# 03_-_CONNECTORS.net
KiCad netlist of a schematic drawn in Altium Designer
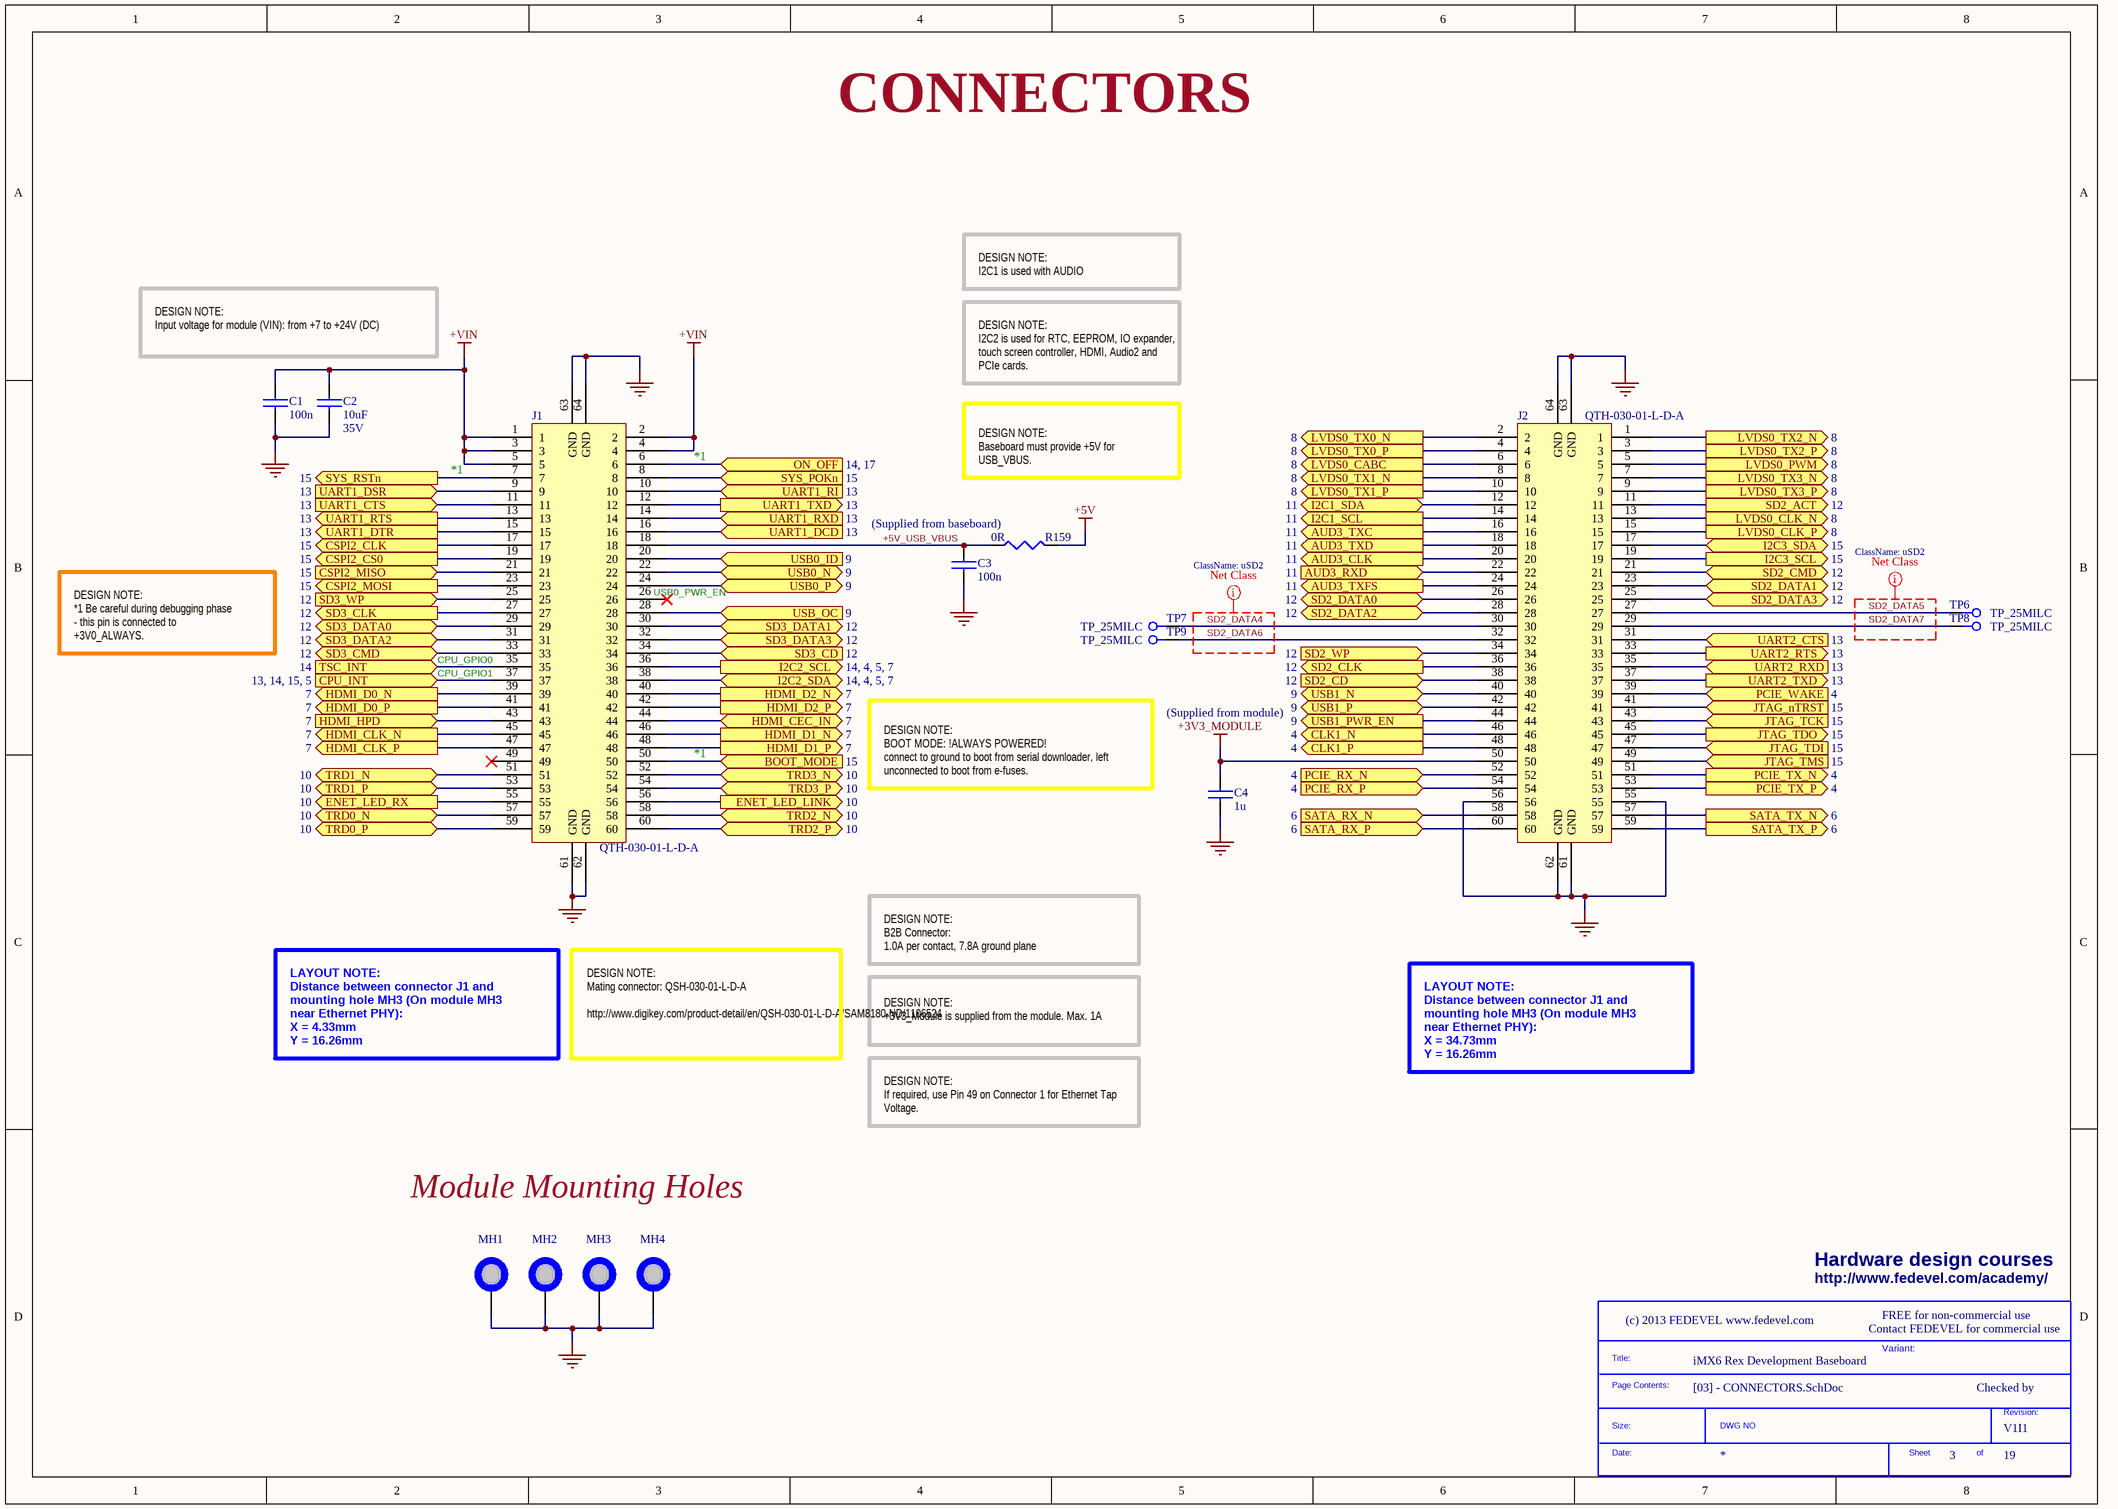
[diagram p0: [03] - CONNECTORS.SchDoc]

(export (version "E")
  (design (tool "Eeschema 10.0.6"))
  (components
    (comp (ref "C1")
      (value "100n")
      (footprint "C0402")
      (description "CAP CER .10UF 50V X5R 10% 0402")
      (fields
        (field (name "MANUFACTURER") "TDK Corporation")
        (field (name "MANUFACTURER PART NUMBER") "C1005X5R1H104K")
      )
      (libsource (lib "Integrated_Library_RF_FEB_2012") (part "C1005X5R1H104K"))
    )
    (comp (ref "C2")
      (value "10uF")
      (footprint "C1206")
      (description "CAP CER 10UF 35V X5R 1206")
      (fields
        (field (name "MANUFACTURER") "Murata Electronics North America")
        (field (name "MANUFACTURER PART NUMBER") "GRM31CR6YA106KA12L")
        (field (name "VOLTAGE - RATED") "35V")
      )
      (libsource (lib "Integrated_Library_RF_FEB_2012") (part "GRM31CR6YA106KA12L"))
    )
    (comp (ref "C3")
      (value "100n")
      (footprint "C0402")
      (description "CAP CER .10UF 50V X5R 10% 0402")
      (fields
        (field (name "MANUFACTURER") "TDK Corporation")
        (field (name "MANUFACTURER PART NUMBER") "C1005X5R1H104K")
      )
      (libsource (lib "Integrated_Library_RF_FEB_2012") (part "C1005X5R1H104K"))
    )
    (comp (ref "C4")
      (value "1u")
      (footprint "C0402")
      (description "CAP CER 1.0UF 16V X5R 0402")
      (fields
        (field (name "MANUFACTURER") "TDK Corporation")
        (field (name "MANUFACTURER PART NUMBER") "C1005X5R1C105K")
      )
      (libsource (lib "Integrated_Library_RF_FEB_2012") (part "C1005X5R1C105K"))
    )
    (comp (ref "J1")
      (value "QTH-030-01-L-D-A")
      (footprint "QTH-030-01-L-D-A")
      (description "CONN HEADER HS .5MM 60POS DL AU")
      (fields (field (name "MANUFACTURER") "Samtec Inc"))
      (libsource (lib "Integrated_Library_RF_FEB_2012") (part "QTH-030-01-L-D-A"))
    )
    (comp (ref "J2")
      (value "QTH-030-01-L-D-A")
      (footprint "QTH-030-01-L-D-A")
      (description "CONN HEADER HS .5MM 60POS DL AU")
      (fields (field (name "MANUFACTURER") "Samtec Inc"))
      (libsource (lib "") (part "QTH-030-01-L-D-A_1"))
    )
    (comp (ref "MH1")
      (value "MH_5MMC_2.2MMD")
      (footprint "MH_5MMD_2.2MMD")
      (description "Mounting Hole 5mm Diameter, 2.2mm Drill")
      (libsource (lib "Integrated_Library_RF_FEB_2012") (part "MH_5MMC_2.2MMD"))
    )
    (comp (ref "MH2")
      (value "MH_5MMC_2.2MMD")
      (footprint "MH_5MMD_2.2MMD")
      (description "Mounting Hole 5mm Diameter, 2.2mm Drill")
      (libsource (lib "Integrated_Library_RF_FEB_2012") (part "MH_5MMC_2.2MMD"))
    )
    (comp (ref "MH3")
      (value "MH_5MMC_2.2MMD")
      (footprint "MH_5MMD_2.2MMD")
      (description "Mounting Hole 5mm Diameter, 2.2mm Drill")
      (libsource (lib "Integrated_Library_RF_FEB_2012") (part "MH_5MMC_2.2MMD"))
    )
    (comp (ref "MH4")
      (value "MH_5MMC_2.2MMD")
      (footprint "MH_5MMD_2.2MMD")
      (description "Mounting Hole 5mm Diameter, 2.2mm Drill")
      (libsource (lib "Integrated_Library_RF_FEB_2012") (part "MH_5MMC_2.2MMD"))
    )
    (comp (ref "R159")
      (value "0R")
      (footprint "R0402")
      (description "RES 0.0 OHM 1/16W 0402 SMD")
      (fields
        (field (name "MANUFACTURER") "Yageo")
        (field (name "MANUFACTURER PART NUMBER") "RC0402JR-070RL")
      )
      (libsource (lib "Integrated_Library_RF_FEB_2012") (part "RC0402JR-070RL"))
    )
    (comp (ref "TP6")
      (value "TP_25MILC")
      (footprint "TP_25C")
      (description "Test Point 25mil")
      (libsource (lib "Integrated_Library_RF_FEB_2012") (part "TP_25MILC"))
    )
    (comp (ref "TP7")
      (value "TP_25MILC")
      (footprint "TP_25C")
      (description "Test Point 25mil")
      (libsource (lib "Integrated_Library_RF_FEB_2012") (part "TP_25MILC"))
    )
    (comp (ref "TP8")
      (value "TP_25MILC")
      (footprint "TP_25C")
      (description "Test Point 25mil")
      (libsource (lib "Integrated_Library_RF_FEB_2012") (part "TP_25MILC"))
    )
    (comp (ref "TP9")
      (value "TP_25MILC")
      (footprint "TP_25C")
      (description "Test Point 25mil")
      (libsource (lib "Integrated_Library_RF_FEB_2012") (part "TP_25MILC"))
    )
  )
  (nets
    (net (code "1") (name "+3V3_MODULE") (class "Default")
      (node (ref "C4") (pin "1") (pinfunction "1_1") (pintype "passive"))
      (node (ref "J2") (pin "50") (pinfunction "50_50") (pintype "passive"))
    )
    (net (code "2") (name "+5V") (class "Default")
      (node (ref "R159") (pin "2") (pinfunction "2_2") (pintype "passive"))
    )
    (net (code "3") (name "+VIN") (class "Default")
      (node (ref "C1") (pin "1") (pinfunction "1_1") (pintype "passive"))
      (node (ref "C2") (pin "1") (pinfunction "1_1") (pintype "passive"))
      (node (ref "J1") (pin "1") (pinfunction "1_1") (pintype "passive"))
      (node (ref "J1") (pin "2") (pinfunction "2_2") (pintype "passive"))
      (node (ref "J1") (pin "3") (pinfunction "3_3") (pintype "passive"))
      (node (ref "J1") (pin "4") (pinfunction "4_4") (pintype "passive"))
      (node (ref "J1") (pin "5") (pinfunction "5_5") (pintype "passive"))
    )
    (net (code "4") (name "/+5V_USB_VBUS") (class "Default")
      (node (ref "C3") (pin "1") (pinfunction "1_1") (pintype "passive"))
      (node (ref "J1") (pin "18") (pinfunction "18_18") (pintype "passive"))
      (node (ref "R159") (pin "1") (pinfunction "1_1") (pintype "passive"))
    )
    (net (code "5") (name "/AUD3_CLK") (class "Default")
      (node (ref "J2") (pin "20") (pinfunction "20_20") (pintype "passive"))
    )
    (net (code "6") (name "/AUD3_RXD") (class "Default")
      (node (ref "J2") (pin "22") (pinfunction "22_22") (pintype "passive"))
    )
    (net (code "7") (name "/AUD3_TXC") (class "Default")
      (node (ref "J2") (pin "16") (pinfunction "16_16") (pintype "passive"))
    )
    (net (code "8") (name "/AUD3_TXD") (class "Default")
      (node (ref "J2") (pin "18") (pinfunction "18_18") (pintype "passive"))
    )
    (net (code "9") (name "/AUD3_TXFS") (class "Default")
      (node (ref "J2") (pin "24") (pinfunction "24_24") (pintype "passive"))
    )
    (net (code "10") (name "/BOOT_MODE") (class "Default")
      (node (ref "J1") (pin "50") (pinfunction "50_50") (pintype "passive"))
    )
    (net (code "11") (name "/CLK1_N") (class "Default")
      (node (ref "J2") (pin "46") (pinfunction "46_46") (pintype "passive"))
    )
    (net (code "12") (name "/CLK1_P") (class "Default")
      (node (ref "J2") (pin "48") (pinfunction "48_48") (pintype "passive"))
    )
    (net (code "13") (name "/CPU_INT") (class "Default")
      (node (ref "J1") (pin "37") (pinfunction "37_37") (pintype "passive"))
    )
    (net (code "14") (name "/CSPI2_CLK") (class "Default")
      (node (ref "J1") (pin "17") (pinfunction "17_17") (pintype "passive"))
    )
    (net (code "15") (name "/CSPI2_CS0") (class "Default")
      (node (ref "J1") (pin "19") (pinfunction "19_19") (pintype "passive"))
    )
    (net (code "16") (name "/CSPI2_MISO") (class "Default")
      (node (ref "J1") (pin "21") (pinfunction "21_21") (pintype "passive"))
    )
    (net (code "17") (name "/CSPI2_MOSI") (class "Default")
      (node (ref "J1") (pin "23") (pinfunction "23_23") (pintype "passive"))
    )
    (net (code "18") (name "/ENET_LED_LINK") (class "Default")
      (node (ref "J1") (pin "56") (pinfunction "56_56") (pintype "passive"))
    )
    (net (code "19") (name "/ENET_LED_RX") (class "Default")
      (node (ref "J1") (pin "55") (pinfunction "55_55") (pintype "passive"))
    )
    (net (code "20") (name "/HDMI_CEC_IN") (class "Default")
      (node (ref "J1") (pin "44") (pinfunction "44_44") (pintype "passive"))
    )
    (net (code "21") (name "/HDMI_CLK_N") (class "Default")
      (node (ref "J1") (pin "45") (pinfunction "45_45") (pintype "passive"))
    )
    (net (code "22") (name "/HDMI_CLK_P") (class "Default")
      (node (ref "J1") (pin "47") (pinfunction "47_47") (pintype "passive"))
    )
    (net (code "23") (name "/HDMI_D0_N") (class "Default")
      (node (ref "J1") (pin "39") (pinfunction "39_39") (pintype "passive"))
    )
    (net (code "24") (name "/HDMI_D0_P") (class "Default")
      (node (ref "J1") (pin "41") (pinfunction "41_41") (pintype "passive"))
    )
    (net (code "25") (name "/HDMI_D1_N") (class "Default")
      (node (ref "J1") (pin "46") (pinfunction "46_46") (pintype "passive"))
    )
    (net (code "26") (name "/HDMI_D1_P") (class "Default")
      (node (ref "J1") (pin "48") (pinfunction "48_48") (pintype "passive"))
    )
    (net (code "27") (name "/HDMI_D2_N") (class "Default")
      (node (ref "J1") (pin "40") (pinfunction "40_40") (pintype "passive"))
    )
    (net (code "28") (name "/HDMI_D2_P") (class "Default")
      (node (ref "J1") (pin "42") (pinfunction "42_42") (pintype "passive"))
    )
    (net (code "29") (name "/HDMI_HPD") (class "Default")
      (node (ref "J1") (pin "43") (pinfunction "43_43") (pintype "passive"))
    )
    (net (code "30") (name "/I2C1_SCL") (class "Default")
      (node (ref "J2") (pin "14") (pinfunction "14_14") (pintype "passive"))
    )
    (net (code "31") (name "/I2C1_SDA") (class "Default")
      (node (ref "J2") (pin "12") (pinfunction "12_12") (pintype "passive"))
    )
    (net (code "32") (name "/I2C2_SCL") (class "Default")
      (node (ref "J1") (pin "36") (pinfunction "36_36") (pintype "passive"))
    )
    (net (code "33") (name "/I2C2_SDA") (class "Default")
      (node (ref "J1") (pin "38") (pinfunction "38_38") (pintype "passive"))
    )
    (net (code "34") (name "/I2C3_SCL") (class "Default")
      (node (ref "J2") (pin "19") (pinfunction "19_19") (pintype "passive"))
    )
    (net (code "35") (name "/I2C3_SDA") (class "Default")
      (node (ref "J2") (pin "17") (pinfunction "17_17") (pintype "passive"))
    )
    (net (code "36") (name "/JTAG_TCK") (class "Default")
      (node (ref "J2") (pin "43") (pinfunction "43_43") (pintype "passive"))
    )
    (net (code "37") (name "/JTAG_TDI") (class "Default")
      (node (ref "J2") (pin "47") (pinfunction "47_47") (pintype "passive"))
    )
    (net (code "38") (name "/JTAG_TDO") (class "Default")
      (node (ref "J2") (pin "45") (pinfunction "45_45") (pintype "passive"))
    )
    (net (code "39") (name "/JTAG_TMS") (class "Default")
      (node (ref "J2") (pin "49") (pinfunction "49_49") (pintype "passive"))
    )
    (net (code "40") (name "/JTAG_nTRST") (class "Default")
      (node (ref "J2") (pin "41") (pinfunction "41_41") (pintype "passive"))
    )
    (net (code "41") (name "/LVDS0_CABC") (class "Default")
      (node (ref "J2") (pin "6") (pinfunction "6_6") (pintype "passive"))
    )
    (net (code "42") (name "/LVDS0_CLK_N") (class "Default")
      (node (ref "J2") (pin "13") (pinfunction "13_13") (pintype "passive"))
    )
    (net (code "43") (name "/LVDS0_CLK_P") (class "Default")
      (node (ref "J2") (pin "15") (pinfunction "15_15") (pintype "passive"))
    )
    (net (code "44") (name "/LVDS0_PWM") (class "Default")
      (node (ref "J2") (pin "5") (pinfunction "5_5") (pintype "passive"))
    )
    (net (code "45") (name "/LVDS0_TX0_N") (class "Default")
      (node (ref "J2") (pin "2") (pinfunction "2_2") (pintype "passive"))
    )
    (net (code "46") (name "/LVDS0_TX0_P") (class "Default")
      (node (ref "J2") (pin "4") (pinfunction "4_4") (pintype "passive"))
    )
    (net (code "47") (name "/LVDS0_TX1_N") (class "Default")
      (node (ref "J2") (pin "8") (pinfunction "8_8") (pintype "passive"))
    )
    (net (code "48") (name "/LVDS0_TX1_P") (class "Default")
      (node (ref "J2") (pin "10") (pinfunction "10_10") (pintype "passive"))
    )
    (net (code "49") (name "/LVDS0_TX2_N") (class "Default")
      (node (ref "J2") (pin "1") (pinfunction "1_1") (pintype "passive"))
    )
    (net (code "50") (name "/LVDS0_TX2_P") (class "Default")
      (node (ref "J2") (pin "3") (pinfunction "3_3") (pintype "passive"))
    )
    (net (code "51") (name "/LVDS0_TX3_N") (class "Default")
      (node (ref "J2") (pin "7") (pinfunction "7_7") (pintype "passive"))
    )
    (net (code "52") (name "/LVDS0_TX3_P") (class "Default")
      (node (ref "J2") (pin "9") (pinfunction "9_9") (pintype "passive"))
    )
    (net (code "53") (name "/ON_OFF") (class "Default")
      (node (ref "J1") (pin "6") (pinfunction "6_6") (pintype "passive"))
    )
    (net (code "54") (name "/PCIE_RX_N") (class "Default")
      (node (ref "J2") (pin "52") (pinfunction "52_52") (pintype "passive"))
    )
    (net (code "55") (name "/PCIE_RX_P") (class "Default")
      (node (ref "J2") (pin "54") (pinfunction "54_54") (pintype "passive"))
    )
    (net (code "56") (name "/PCIE_TX_N") (class "Default")
      (node (ref "J2") (pin "51") (pinfunction "51_51") (pintype "passive"))
    )
    (net (code "57") (name "/PCIE_TX_P") (class "Default")
      (node (ref "J2") (pin "53") (pinfunction "53_53") (pintype "passive"))
    )
    (net (code "58") (name "/PCIE_WAKE") (class "Default")
      (node (ref "J2") (pin "39") (pinfunction "39_39") (pintype "passive"))
    )
    (net (code "59") (name "/SATA_RX_N") (class "Default")
      (node (ref "J2") (pin "58") (pinfunction "58_58") (pintype "passive"))
    )
    (net (code "60") (name "/SATA_RX_P") (class "Default")
      (node (ref "J2") (pin "60") (pinfunction "60_60") (pintype "passive"))
    )
    (net (code "61") (name "/SATA_TX_N") (class "Default")
      (node (ref "J2") (pin "57") (pinfunction "57_57") (pintype "passive"))
    )
    (net (code "62") (name "/SATA_TX_P") (class "Default")
      (node (ref "J2") (pin "59") (pinfunction "59_59") (pintype "passive"))
    )
    (net (code "63") (name "/SD2_ACT") (class "Default")
      (node (ref "J2") (pin "11") (pinfunction "11_11") (pintype "passive"))
    )
    (net (code "64") (name "/SD2_CD") (class "Default")
      (node (ref "J2") (pin "38") (pinfunction "38_38") (pintype "passive"))
    )
    (net (code "65") (name "/SD2_CLK") (class "Default")
      (node (ref "J2") (pin "36") (pinfunction "36_36") (pintype "passive"))
    )
    (net (code "66") (name "/SD2_CMD") (class "Default")
      (node (ref "J2") (pin "21") (pinfunction "21_21") (pintype "passive"))
    )
    (net (code "67") (name "/SD2_DATA0") (class "Default")
      (node (ref "J2") (pin "26") (pinfunction "26_26") (pintype "passive"))
    )
    (net (code "68") (name "/SD2_DATA1") (class "Default")
      (node (ref "J2") (pin "23") (pinfunction "23_23") (pintype "passive"))
    )
    (net (code "69") (name "/SD2_DATA2") (class "Default")
      (node (ref "J2") (pin "28") (pinfunction "28_28") (pintype "passive"))
    )
    (net (code "70") (name "/SD2_DATA3") (class "Default")
      (node (ref "J2") (pin "25") (pinfunction "25_25") (pintype "passive"))
    )
    (net (code "71") (name "/SD2_DATA4") (class "Default")
      (node (ref "J2") (pin "30") (pinfunction "30_30") (pintype "passive"))
      (node (ref "TP7") (pin "1") (pinfunction "1_1") (pintype "passive"))
    )
    (net (code "72") (name "/SD2_DATA5") (class "Default")
      (node (ref "J2") (pin "27") (pinfunction "27_27") (pintype "passive"))
      (node (ref "TP6") (pin "1") (pinfunction "1_1") (pintype "passive"))
    )
    (net (code "73") (name "/SD2_DATA6") (class "Default")
      (node (ref "J2") (pin "32") (pinfunction "32_32") (pintype "passive"))
      (node (ref "TP9") (pin "1") (pinfunction "1_1") (pintype "passive"))
    )
    (net (code "74") (name "/SD2_DATA7") (class "Default")
      (node (ref "J2") (pin "29") (pinfunction "29_29") (pintype "passive"))
      (node (ref "TP8") (pin "1") (pinfunction "1_1") (pintype "passive"))
    )
    (net (code "75") (name "/SD2_WP") (class "Default")
      (node (ref "J2") (pin "34") (pinfunction "34_34") (pintype "passive"))
    )
    (net (code "76") (name "/SD3_CD") (class "Default")
      (node (ref "J1") (pin "34") (pinfunction "34_34") (pintype "passive"))
    )
    (net (code "77") (name "/SD3_CLK") (class "Default")
      (node (ref "J1") (pin "27") (pinfunction "27_27") (pintype "passive"))
    )
    (net (code "78") (name "/SD3_CMD") (class "Default")
      (node (ref "J1") (pin "33") (pinfunction "33_33") (pintype "passive"))
    )
    (net (code "79") (name "/SD3_DATA0") (class "Default")
      (node (ref "J1") (pin "29") (pinfunction "29_29") (pintype "passive"))
    )
    (net (code "80") (name "/SD3_DATA1") (class "Default")
      (node (ref "J1") (pin "30") (pinfunction "30_30") (pintype "passive"))
    )
    (net (code "81") (name "/SD3_DATA2") (class "Default")
      (node (ref "J1") (pin "31") (pinfunction "31_31") (pintype "passive"))
    )
    (net (code "82") (name "/SD3_DATA3") (class "Default")
      (node (ref "J1") (pin "32") (pinfunction "32_32") (pintype "passive"))
    )
    (net (code "83") (name "/SD3_WP") (class "Default")
      (node (ref "J1") (pin "25") (pinfunction "25_25") (pintype "passive"))
    )
    (net (code "84") (name "/SYS_POKn") (class "Default")
      (node (ref "J1") (pin "8") (pinfunction "8_8") (pintype "passive"))
    )
    (net (code "85") (name "/SYS_RSTn") (class "Default")
      (node (ref "J1") (pin "7") (pinfunction "7_7") (pintype "passive"))
    )
    (net (code "86") (name "/TRD0_N") (class "Default")
      (node (ref "J1") (pin "57") (pinfunction "57_57") (pintype "passive"))
    )
    (net (code "87") (name "/TRD0_P") (class "Default")
      (node (ref "J1") (pin "59") (pinfunction "59_59") (pintype "passive"))
    )
    (net (code "88") (name "/TRD1_N") (class "Default")
      (node (ref "J1") (pin "51") (pinfunction "51_51") (pintype "passive"))
    )
    (net (code "89") (name "/TRD1_P") (class "Default")
      (node (ref "J1") (pin "53") (pinfunction "53_53") (pintype "passive"))
    )
    (net (code "90") (name "/TRD2_N") (class "Default")
      (node (ref "J1") (pin "58") (pinfunction "58_58") (pintype "passive"))
    )
    (net (code "91") (name "/TRD2_P") (class "Default")
      (node (ref "J1") (pin "60") (pinfunction "60_60") (pintype "passive"))
    )
    (net (code "92") (name "/TRD3_N") (class "Default")
      (node (ref "J1") (pin "52") (pinfunction "52_52") (pintype "passive"))
    )
    (net (code "93") (name "/TRD3_P") (class "Default")
      (node (ref "J1") (pin "54") (pinfunction "54_54") (pintype "passive"))
    )
    (net (code "94") (name "/TSC_INT") (class "Default")
      (node (ref "J1") (pin "35") (pinfunction "35_35") (pintype "passive"))
    )
    (net (code "95") (name "/UART1_CTS") (class "Default")
      (node (ref "J1") (pin "11") (pinfunction "11_11") (pintype "passive"))
    )
    (net (code "96") (name "/UART1_DCD") (class "Default")
      (node (ref "J1") (pin "16") (pinfunction "16_16") (pintype "passive"))
    )
    (net (code "97") (name "/UART1_DSR") (class "Default")
      (node (ref "J1") (pin "9") (pinfunction "9_9") (pintype "passive"))
    )
    (net (code "98") (name "/UART1_DTR") (class "Default")
      (node (ref "J1") (pin "15") (pinfunction "15_15") (pintype "passive"))
    )
    (net (code "99") (name "/UART1_RI") (class "Default")
      (node (ref "J1") (pin "10") (pinfunction "10_10") (pintype "passive"))
    )
    (net (code "100") (name "/UART1_RTS") (class "Default")
      (node (ref "J1") (pin "13") (pinfunction "13_13") (pintype "passive"))
    )
    (net (code "101") (name "/UART1_RXD") (class "Default")
      (node (ref "J1") (pin "14") (pinfunction "14_14") (pintype "passive"))
    )
    (net (code "102") (name "/UART1_TXD") (class "Default")
      (node (ref "J1") (pin "12") (pinfunction "12_12") (pintype "passive"))
    )
    (net (code "103") (name "/UART2_CTS") (class "Default")
      (node (ref "J2") (pin "31") (pinfunction "31_31") (pintype "passive"))
    )
    (net (code "104") (name "/UART2_RTS") (class "Default")
      (node (ref "J2") (pin "33") (pinfunction "33_33") (pintype "passive"))
    )
    (net (code "105") (name "/UART2_RXD") (class "Default")
      (node (ref "J2") (pin "35") (pinfunction "35_35") (pintype "passive"))
    )
    (net (code "106") (name "/UART2_TXD") (class "Default")
      (node (ref "J2") (pin "37") (pinfunction "37_37") (pintype "passive"))
    )
    (net (code "107") (name "/USB0_ID") (class "Default")
      (node (ref "J1") (pin "20") (pinfunction "20_20") (pintype "passive"))
    )
    (net (code "108") (name "/USB0_N") (class "Default")
      (node (ref "J1") (pin "22") (pinfunction "22_22") (pintype "passive"))
    )
    (net (code "109") (name "/USB0_P") (class "Default")
      (node (ref "J1") (pin "24") (pinfunction "24_24") (pintype "passive"))
    )
    (net (code "110") (name "/USB1_N") (class "Default")
      (node (ref "J2") (pin "40") (pinfunction "40_40") (pintype "passive"))
    )
    (net (code "111") (name "/USB1_P") (class "Default")
      (node (ref "J2") (pin "42") (pinfunction "42_42") (pintype "passive"))
    )
    (net (code "112") (name "/USB1_PWR_EN") (class "Default")
      (node (ref "J2") (pin "44") (pinfunction "44_44") (pintype "passive"))
    )
    (net (code "113") (name "/USB_OC") (class "Default")
      (node (ref "J1") (pin "28") (pinfunction "28_28") (pintype "passive"))
    )
    (net (code "114") (name "GND") (class "Default")
      (node (ref "C1") (pin "2") (pinfunction "2_2") (pintype "passive"))
      (node (ref "C2") (pin "2") (pinfunction "2_2") (pintype "passive"))
      (node (ref "C3") (pin "2") (pinfunction "2_2") (pintype "passive"))
      (node (ref "C4") (pin "2") (pinfunction "2_2") (pintype "passive"))
      (node (ref "J1") (pin "61") (pinfunction "GND_61") (pintype "passive"))
      (node (ref "J1") (pin "62") (pinfunction "GND_62") (pintype "passive"))
      (node (ref "J1") (pin "63") (pinfunction "GND_63") (pintype "passive"))
      (node (ref "J1") (pin "64") (pinfunction "GND_64") (pintype "passive"))
      (node (ref "J2") (pin "55") (pinfunction "55_55") (pintype "passive"))
      (node (ref "J2") (pin "56") (pinfunction "56_56") (pintype "passive"))
      (node (ref "J2") (pin "61") (pinfunction "GND_61") (pintype "passive"))
      (node (ref "J2") (pin "62") (pinfunction "GND_62") (pintype "passive"))
      (node (ref "J2") (pin "63") (pinfunction "GND_63") (pintype "passive"))
      (node (ref "J2") (pin "64") (pinfunction "GND_64") (pintype "passive"))
      (node (ref "MH1") (pin "1") (pinfunction "1_1") (pintype "passive"))
      (node (ref "MH2") (pin "1") (pinfunction "1_1") (pintype "passive"))
      (node (ref "MH3") (pin "1") (pinfunction "1_1") (pintype "passive"))
      (node (ref "MH4") (pin "1") (pinfunction "1_1") (pintype "passive"))
    )
    (net (code "115") (name "unconnected-(J1-HOLE1-Pad65)") (class "Default")
      (node (ref "J1") (pin "65") (pinfunction "HOLE1_65") (pintype "passive"))
    )
    (net (code "116") (name "unconnected-(J1-HOLE2-Pad66)") (class "Default")
      (node (ref "J1") (pin "66") (pinfunction "HOLE2_66") (pintype "passive"))
    )
    (net (code "117") (name "unconnected-(J1-Pad26)") (class "Default")
      (node (ref "J1") (pin "26") (pinfunction "26_26") (pintype "passive+no_connect"))
    )
    (net (code "118") (name "unconnected-(J1-Pad49)") (class "Default")
      (node (ref "J1") (pin "49") (pinfunction "49_49") (pintype "passive+no_connect"))
    )
    (net (code "119") (name "unconnected-(J2-HOLE1-Pad65)") (class "Default")
      (node (ref "J2") (pin "65") (pinfunction "HOLE1_65") (pintype "passive"))
    )
    (net (code "120") (name "unconnected-(J2-HOLE2-Pad66)") (class "Default")
      (node (ref "J2") (pin "66") (pinfunction "HOLE2_66") (pintype "passive"))
    )
  )
)
